# board.net
KiCad netlist of a schematic drawn in EAGLE
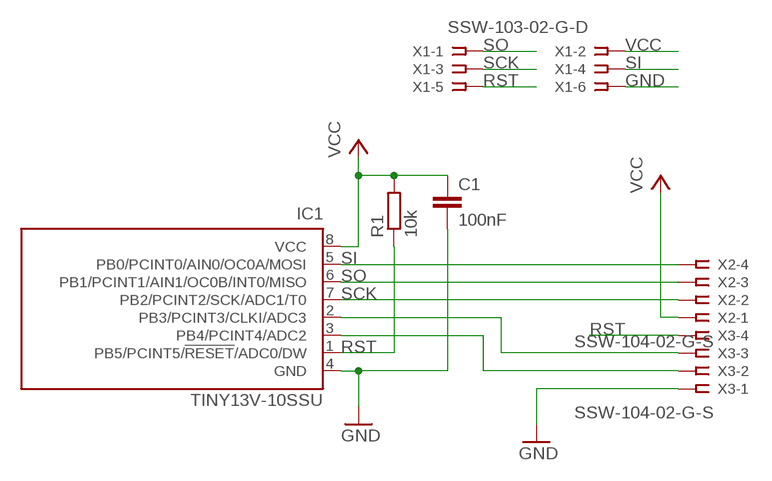
[diagram p0: schematic, sheet 1]

(export (version "E")
  (design (tool "Eeschema 10.0.6"))
  (components
    (comp (ref "C1")
      (value "100nF")
      (footprint "eagle-import:C1206K")
      (libsource (lib "eagle-import") (part "C-EUC1206K"))
    )
    (comp (ref "IC1")
      (value "TINY13V-10SSU")
      (footprint "eagle-import:8S1")
      (fields (field (name "MPN") "ATTINY13V-10SSU"))
      (libsource (lib "eagle-import") (part "TINY13SSUV-10"))
    )
    (comp (ref "R1")
      (value "10k")
      (footprint "eagle-import:R1206")
      (libsource (lib "eagle-import") (part "R-EU_R1206"))
    )
    (comp (ref "X1")
      (value "SSW-103-02-G-D")
      (footprint "eagle-import:SSW-103-02-G-D")
      (fields (field (name "MF") "Samtec Inc."))
      (libsource (lib "eagle-import") (part "SSW-103-02-G-D"))
    )
    (comp (ref "X2")
      (value "SSW-104-02-G-S")
      (footprint "eagle-import:SSW-104-02-G-S")
      (fields (field (name "MF") "Samtec Inc."))
      (libsource (lib "eagle-import") (part "SSW-104-02-G-S"))
    )
    (comp (ref "X3")
      (value "SSW-104-02-G-S")
      (footprint "eagle-import:SSW-104-02-G-S")
      (fields (field (name "MF") "Samtec Inc."))
      (libsource (lib "eagle-import") (part "SSW-104-02-G-S"))
    )
  )
  (nets
    (net (code "1") (name "/RST") (class "Default")
      (node (ref "IC1") (pin "1") (pinfunction "PB5/PCINT5/~{RESET}/ADC0/DW_1") (pintype "bidirectional"))
      (node (ref "R1") (pin "1") (pinfunction "1_1") (pintype "passive"))
      (node (ref "X1") (pin "5") (pinfunction "1_5") (pintype "passive"))
      (node (ref "X3") (pin "4") (pinfunction "1_4") (pintype "passive"))
    )
    (net (code "2") (name "/SCK") (class "Default")
      (node (ref "IC1") (pin "7") (pinfunction "PB2/PCINT2/SCK/ADC1/T0_7") (pintype "bidirectional"))
      (node (ref "X1") (pin "3") (pinfunction "1_3") (pintype "passive"))
      (node (ref "X2") (pin "2") (pinfunction "1_2") (pintype "passive"))
    )
    (net (code "3") (name "/SI") (class "Default")
      (node (ref "IC1") (pin "5") (pinfunction "PB0/PCINT0/AIN0/OC0A/MOSI_5") (pintype "bidirectional"))
      (node (ref "X1") (pin "4") (pinfunction "1_4") (pintype "passive"))
      (node (ref "X2") (pin "4") (pinfunction "1_4") (pintype "passive"))
    )
    (net (code "4") (name "/SO") (class "Default")
      (node (ref "IC1") (pin "6") (pinfunction "PB1/PCINT1/AIN1/OC0B/INT0/MISO_6") (pintype "bidirectional"))
      (node (ref "X1") (pin "1") (pinfunction "1_1") (pintype "passive"))
      (node (ref "X2") (pin "3") (pinfunction "1_3") (pintype "passive"))
    )
    (net (code "5") (name "GND") (class "Default")
      (node (ref "C1") (pin "2") (pinfunction "2_2") (pintype "passive"))
      (node (ref "IC1") (pin "4") (pinfunction "GND_4") (pintype "power_in"))
      (node (ref "X1") (pin "6") (pinfunction "1_6") (pintype "passive"))
      (node (ref "X3") (pin "1") (pinfunction "1_1") (pintype "passive"))
    )
    (net (code "6") (name "Net-(IC1-PB3{slash}PCINT3{slash}CLKI{slash}ADC3)") (class "Default")
      (node (ref "IC1") (pin "2") (pinfunction "PB3/PCINT3/CLKI/ADC3_2") (pintype "bidirectional"))
      (node (ref "X3") (pin "3") (pinfunction "1_3") (pintype "passive"))
    )
    (net (code "7") (name "Net-(IC1-PB4{slash}PCINT4{slash}ADC2)") (class "Default")
      (node (ref "IC1") (pin "3") (pinfunction "PB4/PCINT4/ADC2_3") (pintype "bidirectional"))
      (node (ref "X3") (pin "2") (pinfunction "1_2") (pintype "passive"))
    )
    (net (code "8") (name "VCC") (class "Default")
      (node (ref "C1") (pin "1") (pinfunction "1_1") (pintype "passive"))
      (node (ref "IC1") (pin "8") (pinfunction "VCC_8") (pintype "power_in"))
      (node (ref "R1") (pin "2") (pinfunction "2_2") (pintype "passive"))
      (node (ref "X1") (pin "2") (pinfunction "1_2") (pintype "passive"))
      (node (ref "X2") (pin "1") (pinfunction "1_1") (pintype "passive"))
    )
  )
)
